# rev3.net
KiCad netlist of a schematic drawn in EAGLE
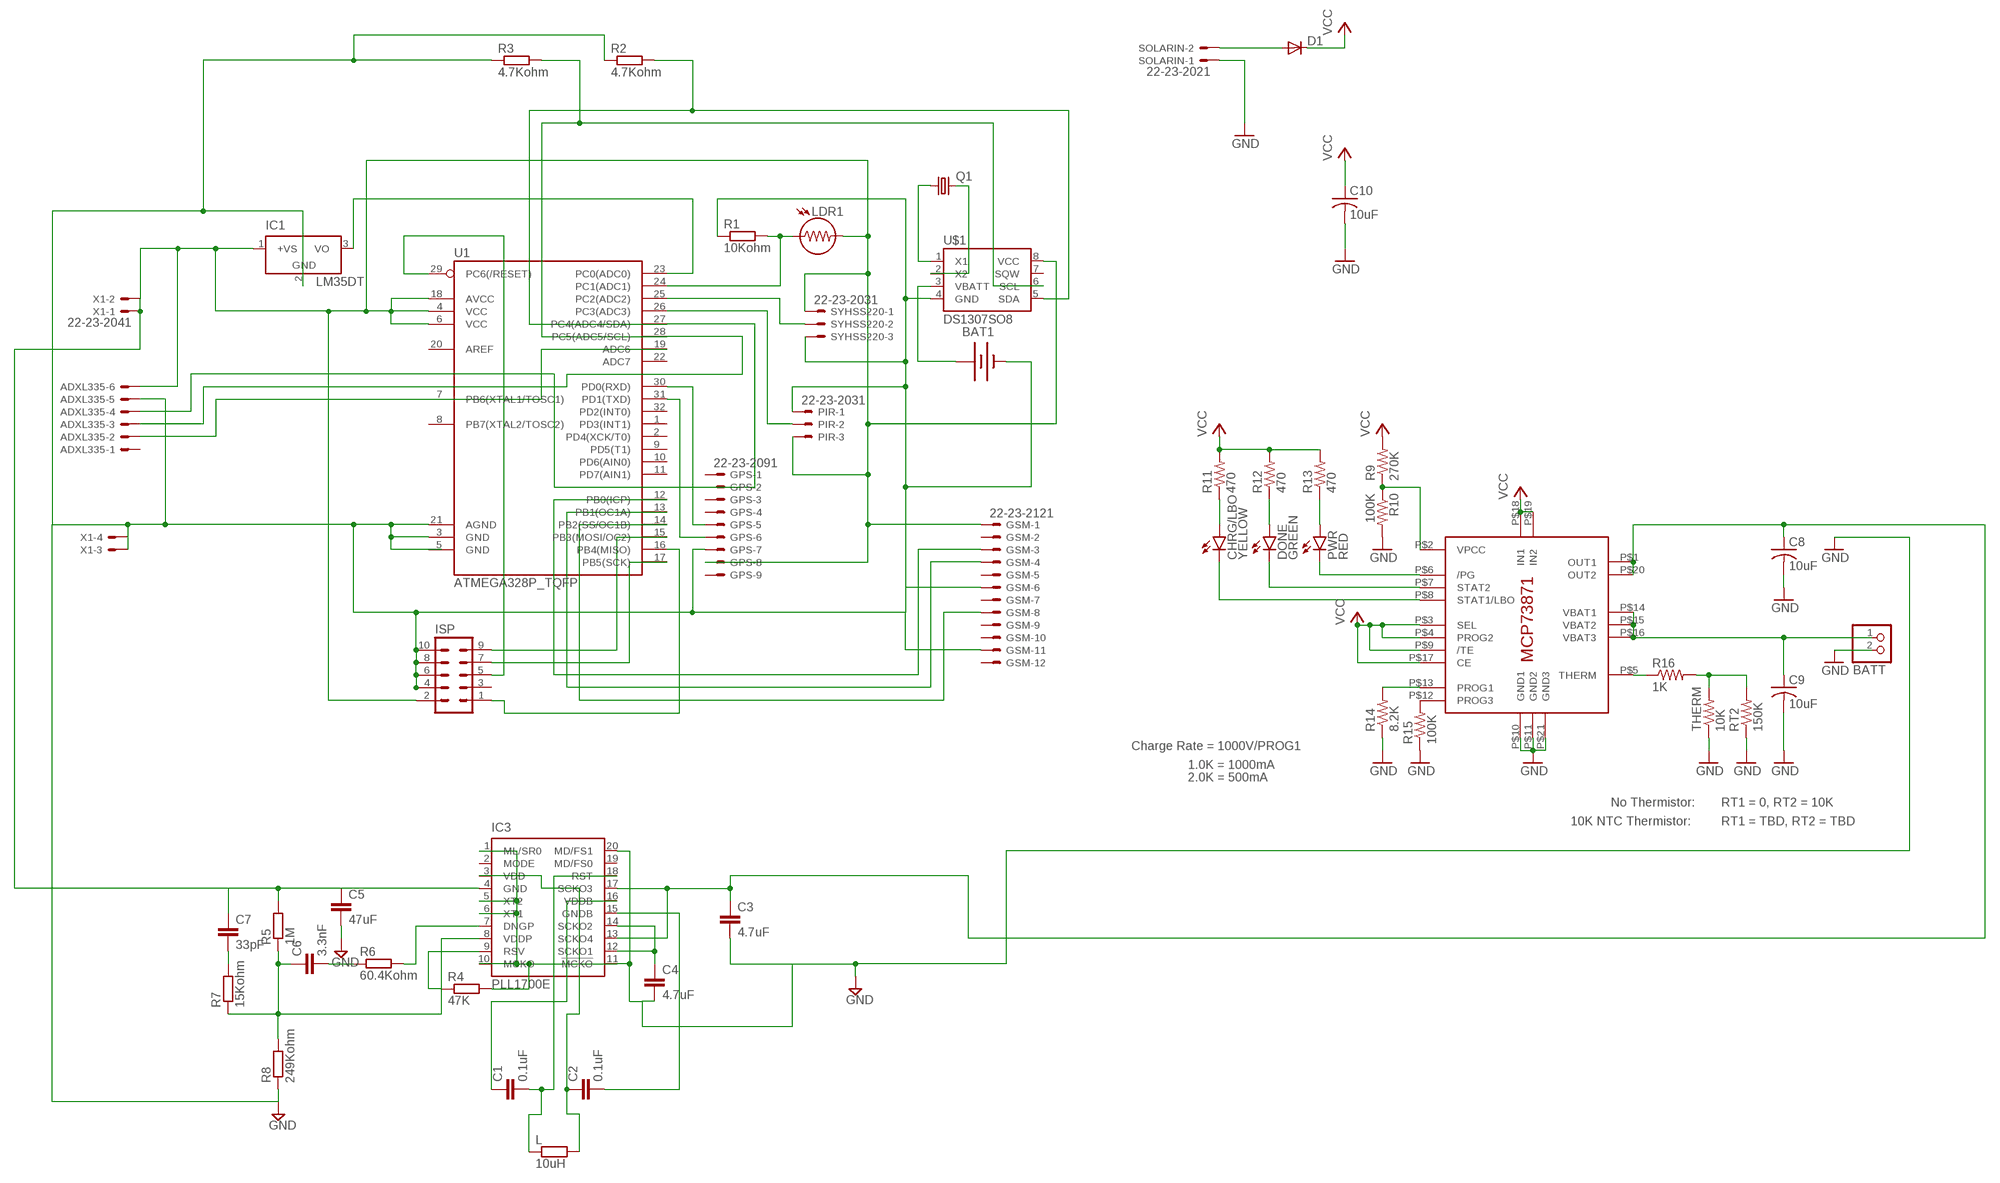
[diagram p0: schematic, sheet 1]

(export (version "E")
  (design (tool "Eeschema 10.0.6"))
  (components
    (comp (ref "ADXL335")
      (value "22-23-2061")
      (footprint "eagle-import:22-23-2061")
      (fields (field (name "MF") "MOLEX"))
      (libsource (lib "eagle-import") (part "22-23-2061"))
    )
    (comp (ref "BAT1")
      (value "BATTERY20PTH")
      (footprint "eagle-import:BATTCOM_20MM_PTH")
      (libsource (lib "eagle-import") (part "BATTERY20PTH"))
    )
    (comp (ref "BATT")
      (value "JST_2PIN-SMT-RA")
      (footprint "eagle-import:JST-PH-2-SMT-RA")
      (libsource (lib "eagle-import") (part "JST_2PIN-SMT-RA"))
    )
    (comp (ref "C1")
      (value "0.1uF")
      (footprint "eagle-import:0402-CAP")
      (libsource (lib "eagle-import") (part "0.1UF-16V(+-10%)(0402)"))
    )
    (comp (ref "C2")
      (value "0.1uF")
      (footprint "eagle-import:0402-CAP")
      (libsource (lib "eagle-import") (part "0.1UF-16V(+-10%)(0402)"))
    )
    (comp (ref "C3")
      (value "4.7uF")
      (footprint "eagle-import:0603-CAP")
      (libsource (lib "eagle-import") (part "4.7UF-6.3V-10%(0603)0603"))
    )
    (comp (ref "C4")
      (value "4.7uF")
      (footprint "eagle-import:0603-CAP")
      (libsource (lib "eagle-import") (part "4.7UF-6.3V-10%(0603)0603"))
    )
    (comp (ref "C5")
      (value "47uF")
      (footprint "eagle-import:0603-CAP")
      (libsource (lib "eagle-import") (part "CAP0603-CAP"))
    )
    (comp (ref "C6")
      (value "3.3nF")
      (footprint "eagle-import:0603-CAP")
      (libsource (lib "eagle-import") (part "3.3NF-100V-10%(0603)"))
    )
    (comp (ref "C7")
      (value "33pF")
      (footprint "eagle-import:0603-CAP")
      (libsource (lib "eagle-import") (part "33PF-50V-5%-(0603)"))
    )
    (comp (ref "C8")
      (value "10uF")
      (footprint "eagle-import:C0805K")
      (libsource (lib "eagle-import") (part "C-USC0805K"))
    )
    (comp (ref "C9")
      (value "10uF")
      (footprint "eagle-import:C0805K")
      (libsource (lib "eagle-import") (part "C-USC0805K"))
    )
    (comp (ref "C10")
      (value "10uF")
      (footprint "eagle-import:C0805K")
      (libsource (lib "eagle-import") (part "C-USC0805K"))
    )
    (comp (ref "CHRG/LBO")
      (value "YELLOW")
      (footprint "eagle-import:LED-1206")
      (libsource (lib "eagle-import") (part "LED-YELLOWLARGE"))
    )
    (comp (ref "D1")
      (value "DIODEPTH")
      (footprint "eagle-import:DIODE-1N4001")
      (libsource (lib "eagle-import") (part "DIODEPTH"))
    )
    (comp (ref "DONE")
      (value "GREEN")
      (footprint "eagle-import:LED-1206")
      (libsource (lib "eagle-import") (part "LED-GREENLARGE"))
    )
    (comp (ref "GPS")
      (value "22-23-2091")
      (footprint "eagle-import:22-23-2091")
      (fields (field (name "MF") "MOLEX"))
      (libsource (lib "eagle-import") (part "22-23-2091"))
    )
    (comp (ref "GSM")
      (value "22-23-2121")
      (footprint "eagle-import:22-23-2121")
      (fields (field (name "MF") "MOLEX"))
      (libsource (lib "eagle-import") (part "22-23-2121"))
    )
    (comp (ref "IC1")
      (value "LM35DT")
      (footprint "eagle-import:TO220V")
      (libsource (lib "eagle-import") (part "LM35DT"))
    )
    (comp (ref "IC2")
      (value "MCP73871")
      (footprint "eagle-import:QFN20_4MM")
      (libsource (lib "eagle-import") (part "MCP73871"))
    )
    (comp (ref "IC3")
      (value "PLL1700E")
      (footprint "eagle-import:SSOP20")
      (fields (field (name "MF") "TEXAS INSTRUMENT CONNECTORS"))
      (libsource (lib "eagle-import") (part "PLL1700E"))
    )
    (comp (ref "ISP")
      (value "ML10")
      (footprint "eagle-import:ML10")
      (libsource (lib "eagle-import") (part "ML10"))
    )
    (comp (ref "L")
      (value "10uH")
      (footprint "eagle-import:R0207_4")
      (libsource (lib "eagle-import") (part "6MM-EU4"))
    )
    (comp (ref "LDR1")
      (value "LDR5MM")
      (footprint "eagle-import:LDR338-54C")
      (libsource (lib "eagle-import") (part "LDR5MM"))
    )
    (comp (ref "PIR")
      (value "22-23-2031")
      (footprint "eagle-import:22-23-2031")
      (fields (field (name "MF") "MOLEX"))
      (libsource (lib "eagle-import") (part "22-23-2031"))
    )
    (comp (ref "PWR")
      (value "RED")
      (footprint "eagle-import:LED-1206")
      (libsource (lib "eagle-import") (part "LED-RED1206"))
    )
    (comp (ref "Q1")
      (value "CRYSTALTC26H")
      (footprint "eagle-import:TC26H")
      (libsource (lib "eagle-import") (part "CRYSTALTC26H"))
    )
    (comp (ref "R1")
      (value "10Kohm")
      (footprint "eagle-import:M1206")
      (libsource (lib "eagle-import") (part "R-EU_M1206"))
    )
    (comp (ref "R2")
      (value "4.7Kohm")
      (footprint "eagle-import:M1206")
      (libsource (lib "eagle-import") (part "R-EU_M1206"))
    )
    (comp (ref "R3")
      (value "4.7Kohm")
      (footprint "eagle-import:M1206")
      (libsource (lib "eagle-import") (part "R-EU_M1206"))
    )
    (comp (ref "R4")
      (value "47K")
      (footprint "eagle-import:M3216")
      (libsource (lib "eagle-import") (part "R-EU_M3216"))
    )
    (comp (ref "R5")
      (value "1M")
      (footprint "eagle-import:M3216")
      (libsource (lib "eagle-import") (part "R-EU_M3216"))
    )
    (comp (ref "R6")
      (value "60.4Kohm")
      (footprint "eagle-import:M3216")
      (libsource (lib "eagle-import") (part "R-EU_M3216"))
    )
    (comp (ref "R7")
      (value "15Kohm")
      (footprint "eagle-import:M1206")
      (libsource (lib "eagle-import") (part "R-EU_M1206"))
    )
    (comp (ref "R8")
      (value "249Kohm")
      (footprint "eagle-import:M1206")
      (libsource (lib "eagle-import") (part "R-EU_M1206"))
    )
    (comp (ref "R9")
      (value "270K")
      (footprint "eagle-import:R0805")
      (libsource (lib "eagle-import") (part "R-US_R0805"))
    )
    (comp (ref "R10")
      (value "100K")
      (footprint "eagle-import:R0805")
      (libsource (lib "eagle-import") (part "R-US_R0805"))
    )
    (comp (ref "R11")
      (value "470")
      (footprint "eagle-import:0603-RES")
      (libsource (lib "eagle-import") (part "470OHM1/10W1%(0603)"))
    )
    (comp (ref "R12")
      (value "470")
      (footprint "eagle-import:0603-RES")
      (libsource (lib "eagle-import") (part "470OHM1/10W1%(0603)"))
    )
    (comp (ref "R13")
      (value "470")
      (footprint "eagle-import:0603-RES")
      (libsource (lib "eagle-import") (part "470OHM1/10W1%(0603)"))
    )
    (comp (ref "R14")
      (value "8.2K")
      (footprint "eagle-import:0603-RES")
      (libsource (lib "eagle-import") (part "8.2KOHM-1/10W-5%(0603)"))
    )
    (comp (ref "R15")
      (value "100K")
      (footprint "eagle-import:R0805")
      (libsource (lib "eagle-import") (part "R-US_R0805"))
    )
    (comp (ref "R16")
      (value "1K")
      (footprint "eagle-import:M0805")
      (libsource (lib "eagle-import") (part "R-US_M0805"))
    )
    (comp (ref "RT2")
      (value "150K")
      (footprint "eagle-import:M0805")
      (libsource (lib "eagle-import") (part "R-US_M0805"))
    )
    (comp (ref "SOLARIN")
      (value "22-23-2021")
      (footprint "eagle-import:22-23-2021")
      (fields (field (name "MF") "MOLEX"))
      (libsource (lib "eagle-import") (part "22-23-2021"))
    )
    (comp (ref "SYHSS220")
      (value "22-23-2031")
      (footprint "eagle-import:22-23-2031")
      (fields (field (name "MF") "MOLEX"))
      (libsource (lib "eagle-import") (part "22-23-2031"))
    )
    (comp (ref "THERM")
      (value "10K")
      (footprint "eagle-import:0805-THM")
      (libsource (lib "eagle-import") (part "R-US_FLIPFLOP"))
    )
    (comp (ref "U$1")
      (value "DS1307SO8")
      (footprint "eagle-import:SO08")
      (libsource (lib "eagle-import") (part "DS1307SO8"))
    )
    (comp (ref "U1")
      (value "ATMEGA328P_TQFP")
      (footprint "eagle-import:TQFP32-08")
      (libsource (lib "eagle-import") (part "ATMEGA328P_TQFP"))
    )
    (comp (ref "X1")
      (value "22-23-2041")
      (footprint "eagle-import:22-23-2041")
      (fields (field (name "MF") "MOLEX"))
      (libsource (lib "eagle-import") (part "22-23-2041"))
    )
  )
  (nets
    (net (code "1") (name "GND") (class "Default")
      (node (ref "ADXL335") (pin "5") (pinfunction "S_5") (pintype "passive"))
      (node (ref "BAT1") (pin "2") (pinfunction "-_2") (pintype "power_in"))
      (node (ref "BATT") (pin "2") (pinfunction "1_2") (pintype "passive"))
      (node (ref "C10") (pin "2") (pinfunction "2_2") (pintype "passive"))
      (node (ref "C3") (pin "2") (pinfunction "2_2") (pintype "passive"))
      (node (ref "C4") (pin "2") (pinfunction "2_2") (pintype "passive"))
      (node (ref "C5") (pin "2") (pinfunction "2_2") (pintype "passive"))
      (node (ref "C8") (pin "2") (pinfunction "2_2") (pintype "passive"))
      (node (ref "C9") (pin "2") (pinfunction "2_2") (pintype "passive"))
      (node (ref "GPS") (pin "7") (pinfunction "S_7") (pintype "passive"))
      (node (ref "GSM") (pin "11") (pinfunction "S_11") (pintype "passive"))
      (node (ref "GSM") (pin "6") (pinfunction "S_6") (pintype "passive"))
      (node (ref "IC1") (pin "2") (pinfunction "GND_2") (pintype "power_in"))
      (node (ref "IC2") (pin "P$10") (pinfunction "GND1_P$10") (pintype "power_in"))
      (node (ref "IC2") (pin "P$11") (pinfunction "GND2_P$11") (pintype "power_in"))
      (node (ref "IC2") (pin "P$21") (pinfunction "GND3_P$21") (pintype "power_in"))
      (node (ref "IC3") (pin "1") (pinfunction "ML/SR0_1") (pintype "input"))
      (node (ref "IC3") (pin "10") (pinfunction "MCKO_10") (pintype "output"))
      (node (ref "IC3") (pin "11") (pinfunction "~{MCKO}_11") (pintype "output"))
      (node (ref "IC3") (pin "20") (pinfunction "MD/FS1_20") (pintype "input"))
      (node (ref "IC3") (pin "5") (pinfunction "XT2_5") (pintype "input"))
      (node (ref "IC3") (pin "6") (pinfunction "XT1_6") (pintype "input"))
      (node (ref "ISP") (pin "10") (pinfunction "10_10") (pintype "passive"))
      (node (ref "ISP") (pin "4") (pinfunction "4_4") (pintype "passive"))
      (node (ref "ISP") (pin "6") (pinfunction "6_6") (pintype "passive"))
      (node (ref "ISP") (pin "8") (pinfunction "8_8") (pintype "passive"))
      (node (ref "PIR") (pin "1") (pinfunction "S_1") (pintype "passive"))
      (node (ref "R1") (pin "1") (pinfunction "1_1") (pintype "passive"))
      (node (ref "R10") (pin "2") (pinfunction "2_2") (pintype "passive"))
      (node (ref "R14") (pin "1") (pinfunction "1_1") (pintype "passive"))
      (node (ref "R15") (pin "1") (pinfunction "1_1") (pintype "passive"))
      (node (ref "R2") (pin "1") (pinfunction "1_1") (pintype "passive"))
      (node (ref "R3") (pin "1") (pinfunction "1_1") (pintype "passive"))
      (node (ref "R4") (pin "2") (pinfunction "2_2") (pintype "passive"))
      (node (ref "R8") (pin "1") (pinfunction "1_1") (pintype "passive"))
      (node (ref "RT2") (pin "1") (pinfunction "1_1") (pintype "passive"))
      (node (ref "SOLARIN") (pin "1") (pinfunction "S_1") (pintype "passive"))
      (node (ref "SYHSS220") (pin "3") (pinfunction "S_3") (pintype "passive"))
      (node (ref "THERM") (pin "1") (pinfunction "1_1") (pintype "passive"))
      (node (ref "U$1") (pin "4") (pinfunction "GND_4") (pintype "bidirectional"))
      (node (ref "U1") (pin "21") (pinfunction "AGND_21") (pintype "bidirectional"))
      (node (ref "U1") (pin "3") (pinfunction "GND_3") (pintype "bidirectional"))
      (node (ref "X1") (pin "3") (pinfunction "S_3") (pintype "passive"))
      (node (ref "X1") (pin "4") (pinfunction "S_4") (pintype "passive"))
    )
    (net (code "2") (name "Net-(ADXL335B-S)") (class "Default")
      (node (ref "ADXL335") (pin "2") (pinfunction "S_2") (pintype "passive"))
      (node (ref "U1") (pin "19") (pinfunction "ADC6_19") (pintype "bidirectional"))
    )
    (net (code "3") (name "Net-(ADXL335C-S)") (class "Default")
      (node (ref "ADXL335") (pin "3") (pinfunction "S_3") (pintype "passive"))
      (node (ref "R3") (pin "2") (pinfunction "2_2") (pintype "passive"))
      (node (ref "U$1") (pin "6") (pinfunction "SCL_6") (pintype "bidirectional"))
      (node (ref "U1") (pin "28") (pinfunction "PC5(ADC5/SCL)_28") (pintype "bidirectional"))
    )
    (net (code "4") (name "Net-(ADXL335D-S)") (class "Default")
      (node (ref "ADXL335") (pin "4") (pinfunction "S_4") (pintype "passive"))
      (node (ref "R2") (pin "2") (pinfunction "2_2") (pintype "passive"))
      (node (ref "U$1") (pin "5") (pinfunction "SDA_5") (pintype "bidirectional"))
      (node (ref "U1") (pin "27") (pinfunction "PC4(ADC4/SDA)_27") (pintype "bidirectional"))
    )
    (net (code "5") (name "Net-(ADXL335F-S)") (class "Default")
      (node (ref "ADXL335") (pin "6") (pinfunction "S_6") (pintype "passive"))
      (node (ref "C5") (pin "1") (pinfunction "1_1") (pintype "passive"))
      (node (ref "C7") (pin "1") (pinfunction "1_1") (pintype "passive"))
      (node (ref "GPS") (pin "8") (pinfunction "S_8") (pintype "passive"))
      (node (ref "GSM") (pin "1") (pinfunction "S_1") (pintype "passive"))
      (node (ref "IC1") (pin "1") (pinfunction "+VS_1") (pintype "input"))
      (node (ref "IC3") (pin "4") (pinfunction "GND_4") (pintype "power_in"))
      (node (ref "ISP") (pin "2") (pinfunction "2_2") (pintype "passive"))
      (node (ref "LDR1") (pin "2") (pinfunction "2_2") (pintype "passive"))
      (node (ref "PIR") (pin "3") (pinfunction "S_3") (pintype "passive"))
      (node (ref "R5") (pin "2") (pinfunction "2_2") (pintype "passive"))
      (node (ref "SYHSS220") (pin "1") (pinfunction "S_1") (pintype "passive"))
      (node (ref "U$1") (pin "8") (pinfunction "VCC_8") (pintype "bidirectional"))
      (node (ref "U1") (pin "18") (pinfunction "AVCC_18") (pintype "bidirectional"))
      (node (ref "U1") (pin "4") (pinfunction "VCC_4") (pintype "bidirectional"))
      (node (ref "U1") (pin "6") (pinfunction "VCC_6") (pintype "bidirectional"))
      (node (ref "X1") (pin "1") (pinfunction "S_1") (pintype "passive"))
      (node (ref "X1") (pin "2") (pinfunction "S_2") (pintype "passive"))
    )
    (net (code "6") (name "Net-(BAT1-+)") (class "Default")
      (node (ref "BAT1") (pin "1") (pinfunction "+_1") (pintype "power_in"))
      (node (ref "U$1") (pin "3") (pinfunction "VBATT_3") (pintype "bidirectional"))
    )
    (net (code "7") (name "Net-(BATT-2)") (class "Default")
      (node (ref "BATT") (pin "1") (pinfunction "2_1") (pintype "passive"))
      (node (ref "C9") (pin "1") (pinfunction "1_1") (pintype "passive"))
      (node (ref "IC2") (pin "P$14") (pinfunction "VBAT1_P$14") (pintype "output"))
      (node (ref "IC2") (pin "P$15") (pinfunction "VBAT2_P$15") (pintype "output"))
      (node (ref "IC2") (pin "P$16") (pinfunction "VBAT3_P$16") (pintype "output"))
    )
    (net (code "8") (name "Net-(C6-Pad2)") (class "Default")
      (node (ref "C6") (pin "2") (pinfunction "2_2") (pintype "passive"))
      (node (ref "R6") (pin "1") (pinfunction "1_1") (pintype "passive"))
    )
    (net (code "9") (name "Net-(C7-Pad2)") (class "Default")
      (node (ref "C7") (pin "2") (pinfunction "2_2") (pintype "passive"))
      (node (ref "R7") (pin "2") (pinfunction "2_2") (pintype "passive"))
    )
    (net (code "10") (name "Net-(CHRG/LBO-PadA)") (class "Default")
      (node (ref "CHRG/LBO") (pin "A") (pinfunction "A_A") (pintype "passive"))
      (node (ref "R11") (pin "1") (pinfunction "1_1") (pintype "passive"))
    )
    (net (code "11") (name "Net-(DONE-PadA)") (class "Default")
      (node (ref "DONE") (pin "A") (pinfunction "A_A") (pintype "passive"))
      (node (ref "R12") (pin "1") (pinfunction "1_1") (pintype "passive"))
    )
    (net (code "12") (name "Net-(GPSE-S)") (class "Default")
      (node (ref "GPS") (pin "5") (pinfunction "S_5") (pintype "passive"))
      (node (ref "U1") (pin "30") (pinfunction "PD0(RXD)_30") (pintype "bidirectional"))
    )
    (net (code "13") (name "Net-(GPSF-S)") (class "Default")
      (node (ref "GPS") (pin "6") (pinfunction "S_6") (pintype "passive"))
      (node (ref "U1") (pin "31") (pinfunction "PD1(TXD)_31") (pintype "bidirectional"))
    )
    (net (code "14") (name "Net-(GSMF-S)") (class "Default")
      (node (ref "GSM") (pin "3") (pinfunction "S_3") (pintype "passive"))
      (node (ref "U1") (pin "12") (pinfunction "PB0(ICP)_12") (pintype "bidirectional"))
    )
    (net (code "15") (name "Net-(GSMG-S)") (class "Default")
      (node (ref "GSM") (pin "4") (pinfunction "S_4") (pintype "passive"))
      (node (ref "U1") (pin "13") (pinfunction "PB1(OC1A)_13") (pintype "bidirectional"))
    )
    (net (code "16") (name "Net-(GSMK-S)") (class "Default")
      (node (ref "GSM") (pin "8") (pinfunction "S_8") (pintype "passive"))
      (node (ref "U1") (pin "14") (pinfunction "PB2(SS/OC1B)_14") (pintype "bidirectional"))
    )
    (net (code "17") (name "Net-(IC1-VO)") (class "Default")
      (node (ref "IC1") (pin "3") (pinfunction "VO_3") (pintype "input"))
      (node (ref "U1") (pin "23") (pinfunction "PC0(ADC0)_23") (pintype "bidirectional"))
    )
    (net (code "18") (name "Net-(IC2-OUT1)") (class "Default")
      (node (ref "C3") (pin "1") (pinfunction "1_1") (pintype "passive"))
      (node (ref "C8") (pin "1") (pinfunction "1_1") (pintype "passive"))
      (node (ref "IC2") (pin "P$1") (pinfunction "OUT1_P$1") (pintype "output"))
      (node (ref "IC2") (pin "P$20") (pinfunction "OUT2_P$20") (pintype "output"))
      (node (ref "IC3") (pin "13") (pinfunction "SCKO4_13") (pintype "output"))
      (node (ref "IC3") (pin "17") (pinfunction "SCKO3_17") (pintype "output"))
    )
    (net (code "19") (name "Net-(IC2-PROG1)") (class "Default")
      (node (ref "IC2") (pin "P$13") (pinfunction "PROG1_P$13") (pintype "input"))
      (node (ref "R14") (pin "2") (pinfunction "2_2") (pintype "passive"))
    )
    (net (code "20") (name "Net-(IC2-PROG3)") (class "Default")
      (node (ref "IC2") (pin "P$12") (pinfunction "PROG3_P$12") (pintype "input"))
      (node (ref "R15") (pin "2") (pinfunction "2_2") (pintype "passive"))
    )
    (net (code "21") (name "Net-(IC2-STAT1{slash}LBO)") (class "Default")
      (node (ref "CHRG/LBO") (pin "C") (pinfunction "C_C") (pintype "passive"))
      (node (ref "IC2") (pin "P$8") (pinfunction "STAT1/LBO_P$8") (pintype "output"))
    )
    (net (code "22") (name "Net-(IC2-STAT2)") (class "Default")
      (node (ref "DONE") (pin "C") (pinfunction "C_C") (pintype "passive"))
      (node (ref "IC2") (pin "P$7") (pinfunction "STAT2_P$7") (pintype "output"))
    )
    (net (code "23") (name "Net-(IC2-THERM)") (class "Default")
      (node (ref "IC2") (pin "P$5") (pinfunction "THERM_P$5") (pintype "input"))
      (node (ref "R16") (pin "1") (pinfunction "1_1") (pintype "passive"))
    )
    (net (code "24") (name "Net-(IC2-VPCC)") (class "Default")
      (node (ref "IC2") (pin "P$2") (pinfunction "VPCC_P$2") (pintype "input"))
      (node (ref "R10") (pin "1") (pinfunction "1_1") (pintype "passive"))
      (node (ref "R9") (pin "1") (pinfunction "1_1") (pintype "passive"))
    )
    (net (code "25") (name "Net-(IC2-{slash}PG)") (class "Default")
      (node (ref "IC2") (pin "P$6") (pinfunction "/PG_P$6") (pintype "output"))
      (node (ref "PWR") (pin "C") (pinfunction "C_C") (pintype "passive"))
    )
    (net (code "26") (name "Net-(IC3-DNGP)") (class "Default")
      (node (ref "IC3") (pin "7") (pinfunction "DNGP_7") (pintype "power_in"))
      (node (ref "R6") (pin "2") (pinfunction "2_2") (pintype "passive"))
    )
    (net (code "27") (name "Net-(IC3-GNDB)") (class "Default")
      (node (ref "C2") (pin "2") (pinfunction "2_2") (pintype "passive"))
      (node (ref "IC3") (pin "15") (pinfunction "GNDB_15") (pintype "power_in"))
    )
    (net (code "28") (name "Net-(IC3-RST)") (class "Default")
      (node (ref "C1") (pin "2") (pinfunction "2_2") (pintype "passive"))
      (node (ref "IC3") (pin "18") (pinfunction "RST_18") (pintype "input"))
      (node (ref "L") (pin "1") (pinfunction "1_1") (pintype "passive"))
    )
    (net (code "29") (name "Net-(IC3-RSV)") (class "Default")
      (node (ref "IC3") (pin "9") (pinfunction "RSV_9") (pintype "passive"))
      (node (ref "R4") (pin "1") (pinfunction "1_1") (pintype "passive"))
    )
    (net (code "30") (name "Net-(IC3-SCKO1)") (class "Default")
      (node (ref "C4") (pin "1") (pinfunction "1_1") (pintype "passive"))
      (node (ref "IC3") (pin "12") (pinfunction "SCKO1_12") (pintype "output"))
      (node (ref "IC3") (pin "14") (pinfunction "SCKO2_14") (pintype "output"))
    )
    (net (code "31") (name "Net-(IC3-VDD)") (class "Default")
      (node (ref "C2") (pin "1") (pinfunction "1_1") (pintype "passive"))
      (node (ref "IC3") (pin "3") (pinfunction "VDD_3") (pintype "input"))
      (node (ref "L") (pin "2") (pinfunction "2_2") (pintype "passive"))
    )
    (net (code "32") (name "Net-(IC3-VDDB)") (class "Default")
      (node (ref "C1") (pin "1") (pinfunction "1_1") (pintype "passive"))
      (node (ref "IC3") (pin "16") (pinfunction "VDDB_16") (pintype "power_in"))
    )
    (net (code "33") (name "Net-(IC3-VDDP)") (class "Default")
      (node (ref "C6") (pin "1") (pinfunction "1_1") (pintype "passive"))
      (node (ref "IC3") (pin "8") (pinfunction "VDDP_8") (pintype "power_in"))
      (node (ref "R5") (pin "1") (pinfunction "1_1") (pintype "passive"))
      (node (ref "R7") (pin "1") (pinfunction "1_1") (pintype "passive"))
      (node (ref "R8") (pin "2") (pinfunction "2_2") (pintype "passive"))
    )
    (net (code "34") (name "Net-(PIRB-S)") (class "Default")
      (node (ref "PIR") (pin "2") (pinfunction "S_2") (pintype "passive"))
      (node (ref "U1") (pin "26") (pinfunction "PC3(ADC3)_26") (pintype "bidirectional"))
    )
    (net (code "35") (name "Net-(PWR-PadA)") (class "Default")
      (node (ref "PWR") (pin "A") (pinfunction "A_A") (pintype "passive"))
      (node (ref "R13") (pin "1") (pinfunction "1_1") (pintype "passive"))
    )
    (net (code "36") (name "Net-(R16-Pad2)") (class "Default")
      (node (ref "R16") (pin "2") (pinfunction "2_2") (pintype "passive"))
      (node (ref "RT2") (pin "2") (pinfunction "2_2") (pintype "passive"))
      (node (ref "THERM") (pin "2") (pinfunction "2_2") (pintype "passive"))
    )
    (net (code "37") (name "Net-(SOLARINB-S)") (class "Default")
      (node (ref "D1") (pin "A") (pinfunction "A_A") (pintype "passive"))
      (node (ref "SOLARIN") (pin "2") (pinfunction "S_2") (pintype "passive"))
    )
    (net (code "38") (name "Net-(SYHSS220B-S)") (class "Default")
      (node (ref "SYHSS220") (pin "2") (pinfunction "S_2") (pintype "passive"))
      (node (ref "U1") (pin "25") (pinfunction "PC2(ADC2)_25") (pintype "bidirectional"))
    )
    (net (code "39") (name "Net-(U$1-X1)") (class "Default")
      (node (ref "Q1") (pin "1") (pinfunction "1_1") (pintype "passive"))
      (node (ref "U$1") (pin "1") (pinfunction "X1_1") (pintype "bidirectional"))
    )
    (net (code "40") (name "Net-(U$1-X2)") (class "Default")
      (node (ref "Q1") (pin "2") (pinfunction "2_2") (pintype "passive"))
      (node (ref "U$1") (pin "2") (pinfunction "X2_2") (pintype "bidirectional"))
    )
    (net (code "41") (name "Net-(U1-PB3(MOSI{slash}OC2))") (class "Default")
      (node (ref "ISP") (pin "9") (pinfunction "9_9") (pintype "passive"))
      (node (ref "U1") (pin "15") (pinfunction "PB3(MOSI/OC2)_15") (pintype "bidirectional"))
    )
    (net (code "42") (name "Net-(U1-PB4(MISO))") (class "Default")
      (node (ref "ISP") (pin "1") (pinfunction "1_1") (pintype "passive"))
      (node (ref "U1") (pin "16") (pinfunction "PB4(MISO)_16") (pintype "bidirectional"))
    )
    (net (code "43") (name "Net-(U1-PB5(SCK))") (class "Default")
      (node (ref "ISP") (pin "7") (pinfunction "7_7") (pintype "passive"))
      (node (ref "U1") (pin "17") (pinfunction "PB5(SCK)_17") (pintype "bidirectional"))
    )
    (net (code "44") (name "Net-(U1-PC1(ADC1))") (class "Default")
      (node (ref "LDR1") (pin "1") (pinfunction "1_1") (pintype "passive"))
      (node (ref "R1") (pin "2") (pinfunction "2_2") (pintype "passive"))
      (node (ref "U1") (pin "24") (pinfunction "PC1(ADC1)_24") (pintype "bidirectional"))
    )
    (net (code "45") (name "Net-(U1-PC6({slash}RESET))") (class "Default")
      (node (ref "ISP") (pin "5") (pinfunction "5_5") (pintype "passive"))
      (node (ref "U1") (pin "29") (pinfunction "PC6(/RESET)_29") (pintype "bidirectional"))
    )
    (net (code "46") (name "VCC") (class "Default")
      (node (ref "C10") (pin "1") (pinfunction "1_1") (pintype "passive"))
      (node (ref "D1") (pin "C") (pinfunction "C_C") (pintype "passive"))
      (node (ref "IC2") (pin "P$17") (pinfunction "CE_P$17") (pintype "input"))
      (node (ref "IC2") (pin "P$18") (pinfunction "IN1_P$18") (pintype "input"))
      (node (ref "IC2") (pin "P$19") (pinfunction "IN2_P$19") (pintype "input"))
      (node (ref "IC2") (pin "P$3") (pinfunction "SEL_P$3") (pintype "input"))
      (node (ref "IC2") (pin "P$4") (pinfunction "PROG2_P$4") (pintype "input"))
      (node (ref "IC2") (pin "P$9") (pinfunction "/TE_P$9") (pintype "input"))
      (node (ref "R11") (pin "2") (pinfunction "2_2") (pintype "passive"))
      (node (ref "R12") (pin "2") (pinfunction "2_2") (pintype "passive"))
      (node (ref "R13") (pin "2") (pinfunction "2_2") (pintype "passive"))
      (node (ref "R9") (pin "2") (pinfunction "2_2") (pintype "passive"))
    )
    (net (code "47") (name "unconnected-(ADXL335A-S-Pad1)") (class "Default")
      (node (ref "ADXL335") (pin "1") (pinfunction "S_1") (pintype "passive"))
    )
    (net (code "48") (name "unconnected-(GPSA-S-Pad1)") (class "Default")
      (node (ref "GPS") (pin "1") (pinfunction "S_1") (pintype "passive"))
    )
    (net (code "49") (name "unconnected-(GPSB-S-Pad2)") (class "Default")
      (node (ref "GPS") (pin "2") (pinfunction "S_2") (pintype "passive"))
    )
    (net (code "50") (name "unconnected-(GPSC-S-Pad3)") (class "Default")
      (node (ref "GPS") (pin "3") (pinfunction "S_3") (pintype "passive"))
    )
    (net (code "51") (name "unconnected-(GPSD-S-Pad4)") (class "Default")
      (node (ref "GPS") (pin "4") (pinfunction "S_4") (pintype "passive"))
    )
    (net (code "52") (name "unconnected-(GPSI-S-Pad9)") (class "Default")
      (node (ref "GPS") (pin "9") (pinfunction "S_9") (pintype "passive"))
    )
    (net (code "53") (name "unconnected-(GSMB-S-Pad10)") (class "Default")
      (node (ref "GSM") (pin "10") (pinfunction "S_10") (pintype "passive"))
    )
    (net (code "54") (name "unconnected-(GSMD-S-Pad12)") (class "Default")
      (node (ref "GSM") (pin "12") (pinfunction "S_12") (pintype "passive"))
    )
    (net (code "55") (name "unconnected-(GSME-S-Pad2)") (class "Default")
      (node (ref "GSM") (pin "2") (pinfunction "S_2") (pintype "passive"))
    )
    (net (code "56") (name "unconnected-(GSMH-S-Pad5)") (class "Default")
      (node (ref "GSM") (pin "5") (pinfunction "S_5") (pintype "passive"))
    )
    (net (code "57") (name "unconnected-(GSMJ-S-Pad7)") (class "Default")
      (node (ref "GSM") (pin "7") (pinfunction "S_7") (pintype "passive"))
    )
    (net (code "58") (name "unconnected-(GSML-S-Pad9)") (class "Default")
      (node (ref "GSM") (pin "9") (pinfunction "S_9") (pintype "passive"))
    )
    (net (code "59") (name "unconnected-(IC3-MD{slash}FS0-Pad19)") (class "Default")
      (node (ref "IC3") (pin "19") (pinfunction "MD/FS0_19") (pintype "input"))
    )
    (net (code "60") (name "unconnected-(IC3-MODE-Pad2)") (class "Default")
      (node (ref "IC3") (pin "2") (pinfunction "MODE_2") (pintype "input"))
    )
    (net (code "61") (name "unconnected-(ISP-Pad3)") (class "Default")
      (node (ref "ISP") (pin "3") (pinfunction "3_3") (pintype "passive"))
    )
    (net (code "62") (name "unconnected-(U$1-SQW-Pad7)") (class "Default")
      (node (ref "U$1") (pin "7") (pinfunction "SQW_7") (pintype "bidirectional"))
    )
    (net (code "63") (name "unconnected-(U1-ADC7-Pad22)") (class "Default")
      (node (ref "U1") (pin "22") (pinfunction "ADC7_22") (pintype "bidirectional"))
    )
    (net (code "64") (name "unconnected-(U1-AREF-Pad20)") (class "Default")
      (node (ref "U1") (pin "20") (pinfunction "AREF_20") (pintype "bidirectional"))
    )
    (net (code "65") (name "unconnected-(U1-GND-Pad5)") (class "Default")
      (node (ref "U1") (pin "5") (pinfunction "GND_5") (pintype "bidirectional"))
    )
    (net (code "66") (name "unconnected-(U1-PB6(XTAL1{slash}TOSC1)-Pad7)") (class "Default")
      (node (ref "U1") (pin "7") (pinfunction "PB6(XTAL1/TOSC1)_7") (pintype "bidirectional"))
    )
    (net (code "67") (name "unconnected-(U1-PB7(XTAL2{slash}TOSC2)-Pad8)") (class "Default")
      (node (ref "U1") (pin "8") (pinfunction "PB7(XTAL2/TOSC2)_8") (pintype "bidirectional"))
    )
    (net (code "68") (name "unconnected-(U1-PD2(INT0)-Pad32)") (class "Default")
      (node (ref "U1") (pin "32") (pinfunction "PD2(INT0)_32") (pintype "bidirectional"))
    )
    (net (code "69") (name "unconnected-(U1-PD3(INT1)-Pad1)") (class "Default")
      (node (ref "U1") (pin "1") (pinfunction "PD3(INT1)_1") (pintype "bidirectional"))
    )
    (net (code "70") (name "unconnected-(U1-PD4(XCK{slash}T0)-Pad2)") (class "Default")
      (node (ref "U1") (pin "2") (pinfunction "PD4(XCK/T0)_2") (pintype "bidirectional"))
    )
    (net (code "71") (name "unconnected-(U1-PD5(T1)-Pad9)") (class "Default")
      (node (ref "U1") (pin "9") (pinfunction "PD5(T1)_9") (pintype "bidirectional"))
    )
    (net (code "72") (name "unconnected-(U1-PD6(AIN0)-Pad10)") (class "Default")
      (node (ref "U1") (pin "10") (pinfunction "PD6(AIN0)_10") (pintype "bidirectional"))
    )
    (net (code "73") (name "unconnected-(U1-PD7(AIN1)-Pad11)") (class "Default")
      (node (ref "U1") (pin "11") (pinfunction "PD7(AIN1)_11") (pintype "bidirectional"))
    )
  )
)
